# vane-anemometer-reeds-new.net
KiCad netlist of a schematic drawn in EAGLE
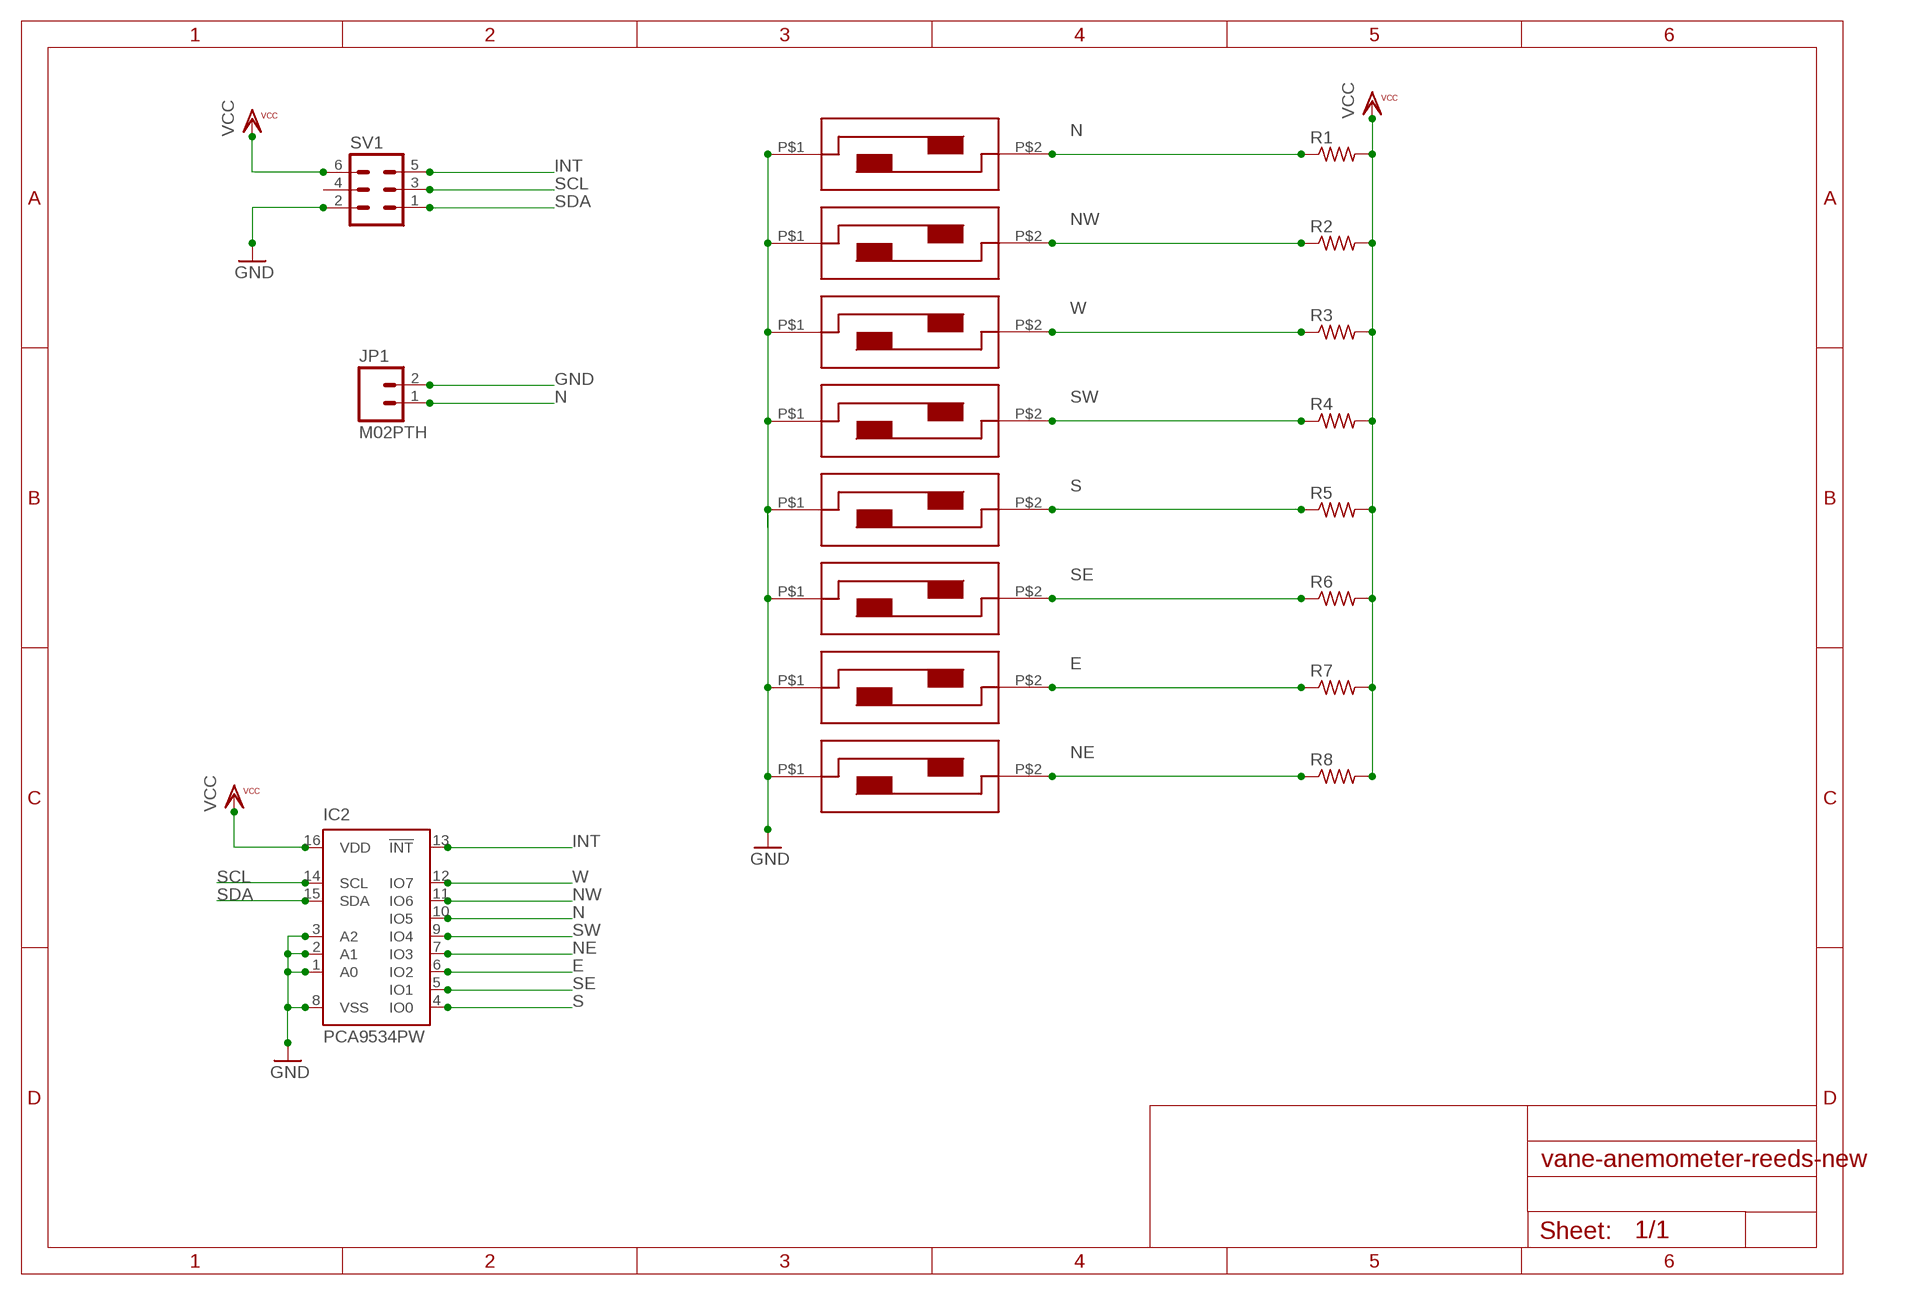
[diagram p0: schematic, sheet 1]

(export (version "E")
  (design (tool "Eeschema 10.0.6"))
  (components
    (comp (ref "EAST")
      (value "SP3-1A16-3A_REED_SWITCH")
      (footprint "eagle-import:MKA-10110")
      (libsource (lib "eagle-import") (part "SP3-1A16-3A_REED_SWITCH"))
    )
    (comp (ref "IC2")
      (value "PCA9534PW")
      (footprint "eagle-import:TSSOP16")
      (libsource (lib "eagle-import") (part "PCA9534PW"))
    )
    (comp (ref "JP1")
      (value "M02PTH")
      (footprint "eagle-import:1X02")
      (libsource (lib "eagle-import") (part "M02PTH"))
    )
    (comp (ref "NORTH")
      (value "SP3-1A16-3A_REED_SWITCH")
      (footprint "eagle-import:MKA-10110")
      (libsource (lib "eagle-import") (part "SP3-1A16-3A_REED_SWITCH"))
    )
    (comp (ref "NORTHEAST")
      (value "SP3-1A16-3A_REED_SWITCH")
      (footprint "eagle-import:MKA-10110")
      (libsource (lib "eagle-import") (part "SP3-1A16-3A_REED_SWITCH"))
    )
    (comp (ref "NORTHWEST")
      (value "SP3-1A16-3A_REED_SWITCH")
      (footprint "eagle-import:MKA-10110")
      (libsource (lib "eagle-import") (part "SP3-1A16-3A_REED_SWITCH"))
    )
    (comp (ref "R1")
      (value "R-US_R1005")
      (footprint "eagle-import:R1005")
      (libsource (lib "eagle-import") (part "R-US_R1005"))
    )
    (comp (ref "R2")
      (value "R-US_R1005")
      (footprint "eagle-import:R1005")
      (libsource (lib "eagle-import") (part "R-US_R1005"))
    )
    (comp (ref "R3")
      (value "R-US_R1005")
      (footprint "eagle-import:R1005")
      (libsource (lib "eagle-import") (part "R-US_R1005"))
    )
    (comp (ref "R4")
      (value "R-US_R1005")
      (footprint "eagle-import:R1005")
      (libsource (lib "eagle-import") (part "R-US_R1005"))
    )
    (comp (ref "R5")
      (value "R-US_R1005")
      (footprint "eagle-import:R1005")
      (libsource (lib "eagle-import") (part "R-US_R1005"))
    )
    (comp (ref "R6")
      (value "R-US_R1005")
      (footprint "eagle-import:R1005")
      (libsource (lib "eagle-import") (part "R-US_R1005"))
    )
    (comp (ref "R7")
      (value "R-US_R1005")
      (footprint "eagle-import:R1005")
      (libsource (lib "eagle-import") (part "R-US_R1005"))
    )
    (comp (ref "R8")
      (value "R-US_R1005")
      (footprint "eagle-import:R1005")
      (libsource (lib "eagle-import") (part "R-US_R1005"))
    )
    (comp (ref "SOUTH")
      (value "SP3-1A16-3A_REED_SWITCH")
      (footprint "eagle-import:MKA-10110")
      (libsource (lib "eagle-import") (part "SP3-1A16-3A_REED_SWITCH"))
    )
    (comp (ref "SOUTHEAST")
      (value "SP3-1A16-3A_REED_SWITCH")
      (footprint "eagle-import:MKA-10110")
      (libsource (lib "eagle-import") (part "SP3-1A16-3A_REED_SWITCH"))
    )
    (comp (ref "SOUTHWEST")
      (value "SP3-1A16-3A_REED_SWITCH")
      (footprint "eagle-import:MKA-10110")
      (libsource (lib "eagle-import") (part "SP3-1A16-3A_REED_SWITCH"))
    )
    (comp (ref "SV1")
      (value "MA03-2")
      (footprint "eagle-import:MA03-2")
      (libsource (lib "eagle-import") (part "MA03-2"))
    )
    (comp (ref "WEST")
      (value "SP3-1A16-3A_REED_SWITCH")
      (footprint "eagle-import:MKA-10110")
      (libsource (lib "eagle-import") (part "SP3-1A16-3A_REED_SWITCH"))
    )
  )
  (nets
    (net (code "1") (name "/E") (class "Default")
      (node (ref "EAST") (pin "P$2") (pinfunction "P$2_P$2") (pintype "bidirectional"))
      (node (ref "IC2") (pin "6") (pinfunction "IO2_6") (pintype "bidirectional"))
      (node (ref "R7") (pin "1") (pinfunction "1_1") (pintype "passive"))
    )
    (net (code "2") (name "/INT") (class "Default")
      (node (ref "IC2") (pin "13") (pinfunction "~{INT}_13") (pintype "open_collector"))
      (node (ref "SV1") (pin "5") (pinfunction "5_5") (pintype "passive"))
    )
    (net (code "3") (name "/N") (class "Default")
      (node (ref "IC2") (pin "10") (pinfunction "IO5_10") (pintype "bidirectional"))
      (node (ref "JP1") (pin "1") (pinfunction "1_1") (pintype "passive"))
      (node (ref "NORTH") (pin "P$2") (pinfunction "P$2_P$2") (pintype "bidirectional"))
      (node (ref "R1") (pin "1") (pinfunction "1_1") (pintype "passive"))
    )
    (net (code "4") (name "/NE") (class "Default")
      (node (ref "IC2") (pin "7") (pinfunction "IO3_7") (pintype "bidirectional"))
      (node (ref "NORTHEAST") (pin "P$2") (pinfunction "P$2_P$2") (pintype "bidirectional"))
      (node (ref "R8") (pin "1") (pinfunction "1_1") (pintype "passive"))
    )
    (net (code "5") (name "/NW") (class "Default")
      (node (ref "IC2") (pin "11") (pinfunction "IO6_11") (pintype "bidirectional"))
      (node (ref "NORTHWEST") (pin "P$2") (pinfunction "P$2_P$2") (pintype "bidirectional"))
      (node (ref "R2") (pin "1") (pinfunction "1_1") (pintype "passive"))
    )
    (net (code "6") (name "/S") (class "Default")
      (node (ref "IC2") (pin "4") (pinfunction "IO0_4") (pintype "bidirectional"))
      (node (ref "R5") (pin "1") (pinfunction "1_1") (pintype "passive"))
      (node (ref "SOUTH") (pin "P$2") (pinfunction "P$2_P$2") (pintype "bidirectional"))
    )
    (net (code "7") (name "/SCL") (class "Default")
      (node (ref "IC2") (pin "14") (pinfunction "SCL_14") (pintype "input"))
      (node (ref "SV1") (pin "3") (pinfunction "3_3") (pintype "passive"))
    )
    (net (code "8") (name "/SDA") (class "Default")
      (node (ref "IC2") (pin "15") (pinfunction "SDA_15") (pintype "bidirectional"))
      (node (ref "SV1") (pin "1") (pinfunction "1_1") (pintype "passive"))
    )
    (net (code "9") (name "/SE") (class "Default")
      (node (ref "IC2") (pin "5") (pinfunction "IO1_5") (pintype "bidirectional"))
      (node (ref "R6") (pin "1") (pinfunction "1_1") (pintype "passive"))
      (node (ref "SOUTHEAST") (pin "P$2") (pinfunction "P$2_P$2") (pintype "bidirectional"))
    )
    (net (code "10") (name "/SW") (class "Default")
      (node (ref "IC2") (pin "9") (pinfunction "IO4_9") (pintype "bidirectional"))
      (node (ref "R4") (pin "1") (pinfunction "1_1") (pintype "passive"))
      (node (ref "SOUTHWEST") (pin "P$2") (pinfunction "P$2_P$2") (pintype "bidirectional"))
    )
    (net (code "11") (name "/W") (class "Default")
      (node (ref "IC2") (pin "12") (pinfunction "IO7_12") (pintype "bidirectional"))
      (node (ref "R3") (pin "1") (pinfunction "1_1") (pintype "passive"))
      (node (ref "WEST") (pin "P$2") (pinfunction "P$2_P$2") (pintype "bidirectional"))
    )
    (net (code "12") (name "GND") (class "Default")
      (node (ref "EAST") (pin "P$1") (pinfunction "P$1_P$1") (pintype "bidirectional"))
      (node (ref "IC2") (pin "1") (pinfunction "A0_1") (pintype "input"))
      (node (ref "IC2") (pin "2") (pinfunction "A1_2") (pintype "input"))
      (node (ref "IC2") (pin "3") (pinfunction "A2_3") (pintype "input"))
      (node (ref "IC2") (pin "8") (pinfunction "VSS_8") (pintype "power_in"))
      (node (ref "JP1") (pin "2") (pinfunction "2_2") (pintype "passive"))
      (node (ref "NORTH") (pin "P$1") (pinfunction "P$1_P$1") (pintype "bidirectional"))
      (node (ref "NORTHEAST") (pin "P$1") (pinfunction "P$1_P$1") (pintype "bidirectional"))
      (node (ref "NORTHWEST") (pin "P$1") (pinfunction "P$1_P$1") (pintype "bidirectional"))
      (node (ref "SOUTH") (pin "P$1") (pinfunction "P$1_P$1") (pintype "bidirectional"))
      (node (ref "SOUTHEAST") (pin "P$1") (pinfunction "P$1_P$1") (pintype "bidirectional"))
      (node (ref "SOUTHWEST") (pin "P$1") (pinfunction "P$1_P$1") (pintype "bidirectional"))
      (node (ref "SV1") (pin "2") (pinfunction "2_2") (pintype "passive"))
      (node (ref "WEST") (pin "P$1") (pinfunction "P$1_P$1") (pintype "bidirectional"))
    )
    (net (code "13") (name "VCC") (class "Default")
      (node (ref "IC2") (pin "16") (pinfunction "VDD_16") (pintype "power_in"))
      (node (ref "R1") (pin "2") (pinfunction "2_2") (pintype "passive"))
      (node (ref "R2") (pin "2") (pinfunction "2_2") (pintype "passive"))
      (node (ref "R3") (pin "2") (pinfunction "2_2") (pintype "passive"))
      (node (ref "R4") (pin "2") (pinfunction "2_2") (pintype "passive"))
      (node (ref "R5") (pin "2") (pinfunction "2_2") (pintype "passive"))
      (node (ref "R6") (pin "2") (pinfunction "2_2") (pintype "passive"))
      (node (ref "R7") (pin "2") (pinfunction "2_2") (pintype "passive"))
      (node (ref "R8") (pin "2") (pinfunction "2_2") (pintype "passive"))
      (node (ref "SV1") (pin "6") (pinfunction "6_6") (pintype "passive"))
    )
    (net (code "14") (name "unconnected-(SV1-Pad4)") (class "Default")
      (node (ref "SV1") (pin "4") (pinfunction "4_4") (pintype "passive"))
    )
  )
)
